# Radial-V_Bus.net
KiCad netlist of a schematic drawn in EAGLE
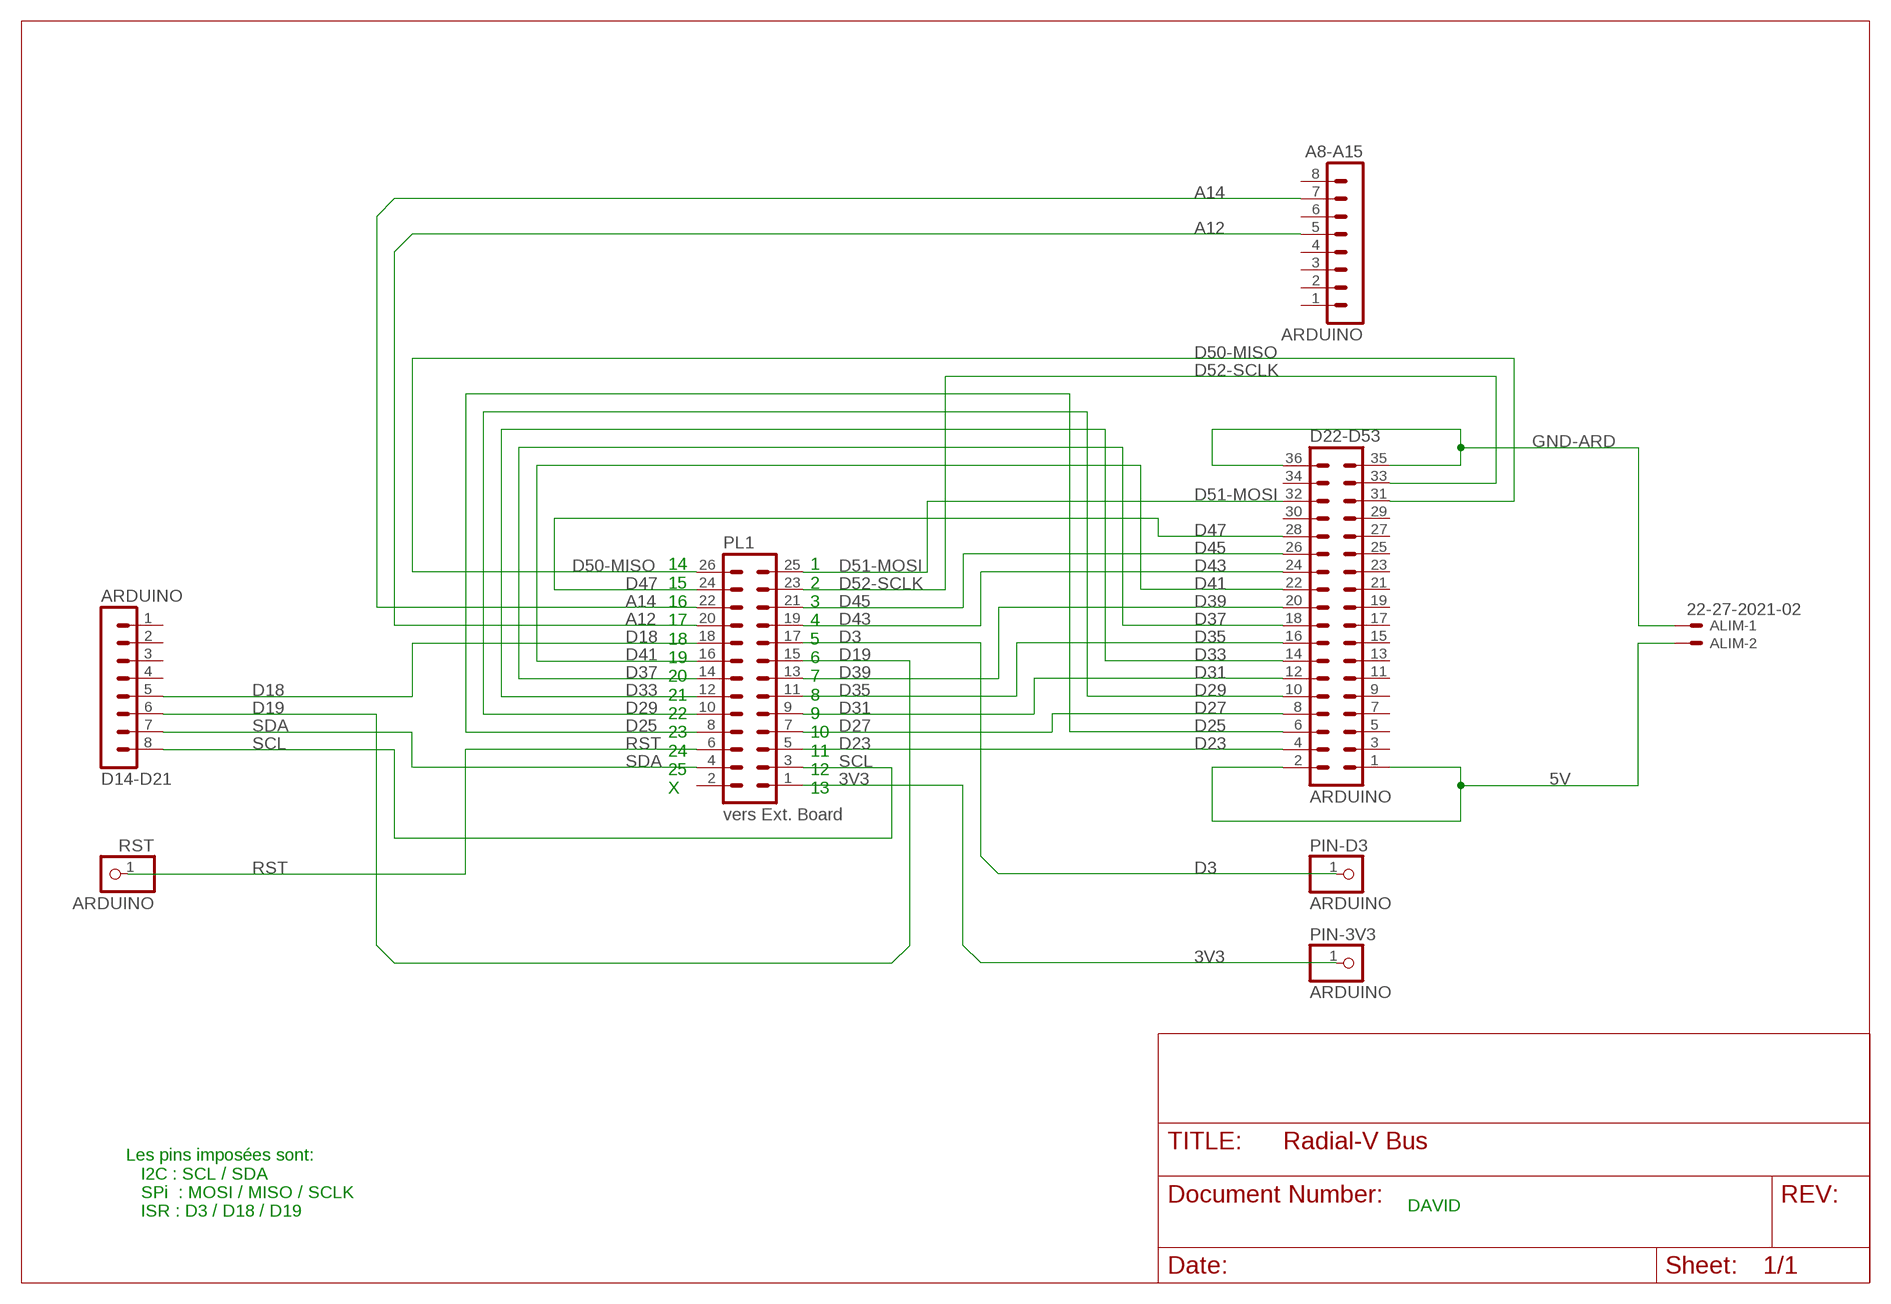
[diagram p0: schematic, sheet 1]

(export (version "E")
  (design (tool "Eeschema 10.0.6"))
  (components
    (comp (ref "A8-A15")
      (value "ARDUINO")
      (footprint "eagle-import:MA08-1")
      (libsource (lib "eagle-import") (part "MA08-1"))
    )
    (comp (ref "ALIM")
      (value "22-27-2021-02")
      (footprint "eagle-import:6410-02")
      (libsource (lib "eagle-import") (part "22-?-0227-2021"))
    )
    (comp (ref "D14-D21")
      (value "ARDUINO")
      (footprint "eagle-import:MA08-1")
      (libsource (lib "eagle-import") (part "MA08-1"))
    )
    (comp (ref "D22-D53")
      (value "ARDUINO")
      (footprint "eagle-import:MA18-2")
      (libsource (lib "eagle-import") (part "MA18-2"))
    )
    (comp (ref "PIN-3V3")
      (value "ARDUINO")
      (footprint "eagle-import:1X01")
      (libsource (lib "eagle-import") (part "PINHD-1X1"))
    )
    (comp (ref "PIN-D3")
      (value "ARDUINO")
      (footprint "eagle-import:1X01")
      (libsource (lib "eagle-import") (part "PINHD-1X1"))
    )
    (comp (ref "PL1")
      (value "vers Ext. Board")
      (footprint "eagle-import:26H")
      (libsource (lib "eagle-import") (part "26H"))
    )
    (comp (ref "RST")
      (value "ARDUINO")
      (footprint "eagle-import:1X01")
      (libsource (lib "eagle-import") (part "PINHD-1X1"))
    )
  )
  (nets
    (net (code "1") (name "/3V3") (class "Default")
      (node (ref "PIN-3V3") (pin "1") (pinfunction "1_1") (pintype "passive"))
      (node (ref "PL1") (pin "1") (pinfunction "1_1") (pintype "passive"))
    )
    (net (code "2") (name "/5V") (class "Default")
      (node (ref "ALIM") (pin "2") (pinfunction "S_2") (pintype "passive"))
      (node (ref "D22-D53") (pin "1") (pinfunction "1_1") (pintype "passive"))
      (node (ref "D22-D53") (pin "2") (pinfunction "2_2") (pintype "passive"))
    )
    (net (code "3") (name "/A12") (class "Default")
      (node (ref "A8-A15") (pin "5") (pinfunction "5_5") (pintype "passive"))
      (node (ref "PL1") (pin "20") (pinfunction "20_20") (pintype "passive"))
    )
    (net (code "4") (name "/A14") (class "Default")
      (node (ref "A8-A15") (pin "7") (pinfunction "7_7") (pintype "passive"))
      (node (ref "PL1") (pin "22") (pinfunction "22_22") (pintype "passive"))
    )
    (net (code "5") (name "/D3") (class "Default")
      (node (ref "PIN-D3") (pin "1") (pinfunction "1_1") (pintype "passive"))
      (node (ref "PL1") (pin "17") (pinfunction "17_17") (pintype "passive"))
    )
    (net (code "6") (name "/D18") (class "Default")
      (node (ref "D14-D21") (pin "5") (pinfunction "5_5") (pintype "passive"))
      (node (ref "PL1") (pin "18") (pinfunction "18_18") (pintype "passive"))
    )
    (net (code "7") (name "/D19") (class "Default")
      (node (ref "D14-D21") (pin "6") (pinfunction "6_6") (pintype "passive"))
      (node (ref "PL1") (pin "15") (pinfunction "15_15") (pintype "passive"))
    )
    (net (code "8") (name "/D23") (class "Default")
      (node (ref "D22-D53") (pin "4") (pinfunction "4_4") (pintype "passive"))
      (node (ref "PL1") (pin "5") (pinfunction "5_5") (pintype "passive"))
    )
    (net (code "9") (name "/D25") (class "Default")
      (node (ref "D22-D53") (pin "6") (pinfunction "6_6") (pintype "passive"))
      (node (ref "PL1") (pin "8") (pinfunction "8_8") (pintype "passive"))
    )
    (net (code "10") (name "/D27") (class "Default")
      (node (ref "D22-D53") (pin "8") (pinfunction "8_8") (pintype "passive"))
      (node (ref "PL1") (pin "7") (pinfunction "7_7") (pintype "passive"))
    )
    (net (code "11") (name "/D29") (class "Default")
      (node (ref "D22-D53") (pin "10") (pinfunction "10_10") (pintype "passive"))
      (node (ref "PL1") (pin "10") (pinfunction "10_10") (pintype "passive"))
    )
    (net (code "12") (name "/D31") (class "Default")
      (node (ref "D22-D53") (pin "12") (pinfunction "12_12") (pintype "passive"))
      (node (ref "PL1") (pin "9") (pinfunction "9_9") (pintype "passive"))
    )
    (net (code "13") (name "/D33") (class "Default")
      (node (ref "D22-D53") (pin "14") (pinfunction "14_14") (pintype "passive"))
      (node (ref "PL1") (pin "12") (pinfunction "12_12") (pintype "passive"))
    )
    (net (code "14") (name "/D35") (class "Default")
      (node (ref "D22-D53") (pin "16") (pinfunction "16_16") (pintype "passive"))
      (node (ref "PL1") (pin "11") (pinfunction "11_11") (pintype "passive"))
    )
    (net (code "15") (name "/D37") (class "Default")
      (node (ref "D22-D53") (pin "18") (pinfunction "18_18") (pintype "passive"))
      (node (ref "PL1") (pin "14") (pinfunction "14_14") (pintype "passive"))
    )
    (net (code "16") (name "/D39") (class "Default")
      (node (ref "D22-D53") (pin "20") (pinfunction "20_20") (pintype "passive"))
      (node (ref "PL1") (pin "13") (pinfunction "13_13") (pintype "passive"))
    )
    (net (code "17") (name "/D41") (class "Default")
      (node (ref "D22-D53") (pin "22") (pinfunction "22_22") (pintype "passive"))
      (node (ref "PL1") (pin "16") (pinfunction "16_16") (pintype "passive"))
    )
    (net (code "18") (name "/D43") (class "Default")
      (node (ref "D22-D53") (pin "24") (pinfunction "24_24") (pintype "passive"))
      (node (ref "PL1") (pin "19") (pinfunction "19_19") (pintype "passive"))
    )
    (net (code "19") (name "/D45") (class "Default")
      (node (ref "D22-D53") (pin "26") (pinfunction "26_26") (pintype "passive"))
      (node (ref "PL1") (pin "21") (pinfunction "21_21") (pintype "passive"))
    )
    (net (code "20") (name "/D47") (class "Default")
      (node (ref "D22-D53") (pin "28") (pinfunction "28_28") (pintype "passive"))
      (node (ref "PL1") (pin "24") (pinfunction "24_24") (pintype "passive"))
    )
    (net (code "21") (name "/D50-MISO") (class "Default")
      (node (ref "D22-D53") (pin "31") (pinfunction "31_31") (pintype "passive"))
      (node (ref "PL1") (pin "26") (pinfunction "26_26") (pintype "passive"))
    )
    (net (code "22") (name "/D51-MOSI") (class "Default")
      (node (ref "D22-D53") (pin "32") (pinfunction "32_32") (pintype "passive"))
      (node (ref "PL1") (pin "25") (pinfunction "25_25") (pintype "passive"))
    )
    (net (code "23") (name "/D52-SCLK") (class "Default")
      (node (ref "D22-D53") (pin "33") (pinfunction "33_33") (pintype "passive"))
      (node (ref "PL1") (pin "23") (pinfunction "23_23") (pintype "passive"))
    )
    (net (code "24") (name "/GND-ARD") (class "Default")
      (node (ref "ALIM") (pin "1") (pinfunction "S_1") (pintype "passive"))
      (node (ref "D22-D53") (pin "35") (pinfunction "35_35") (pintype "passive"))
      (node (ref "D22-D53") (pin "36") (pinfunction "36_36") (pintype "passive"))
    )
    (net (code "25") (name "/RST") (class "Default")
      (node (ref "PL1") (pin "6") (pinfunction "6_6") (pintype "passive"))
      (node (ref "RST") (pin "1") (pinfunction "1_1") (pintype "passive"))
    )
    (net (code "26") (name "/SCL") (class "Default")
      (node (ref "D14-D21") (pin "8") (pinfunction "8_8") (pintype "passive"))
      (node (ref "PL1") (pin "3") (pinfunction "3_3") (pintype "passive"))
    )
    (net (code "27") (name "/SDA") (class "Default")
      (node (ref "D14-D21") (pin "7") (pinfunction "7_7") (pintype "passive"))
      (node (ref "PL1") (pin "4") (pinfunction "4_4") (pintype "passive"))
    )
    (net (code "28") (name "unconnected-(A8-A15-Pad1)") (class "Default")
      (node (ref "A8-A15") (pin "1") (pinfunction "1_1") (pintype "passive"))
    )
    (net (code "29") (name "unconnected-(A8-A15-Pad2)") (class "Default")
      (node (ref "A8-A15") (pin "2") (pinfunction "2_2") (pintype "passive"))
    )
    (net (code "30") (name "unconnected-(A8-A15-Pad3)") (class "Default")
      (node (ref "A8-A15") (pin "3") (pinfunction "3_3") (pintype "passive"))
    )
    (net (code "31") (name "unconnected-(A8-A15-Pad4)") (class "Default")
      (node (ref "A8-A15") (pin "4") (pinfunction "4_4") (pintype "passive"))
    )
    (net (code "32") (name "unconnected-(A8-A15-Pad6)") (class "Default")
      (node (ref "A8-A15") (pin "6") (pinfunction "6_6") (pintype "passive"))
    )
    (net (code "33") (name "unconnected-(A8-A15-Pad8)") (class "Default")
      (node (ref "A8-A15") (pin "8") (pinfunction "8_8") (pintype "passive"))
    )
    (net (code "34") (name "unconnected-(D14-D21-Pad1)") (class "Default")
      (node (ref "D14-D21") (pin "1") (pinfunction "1_1") (pintype "passive"))
    )
    (net (code "35") (name "unconnected-(D14-D21-Pad2)") (class "Default")
      (node (ref "D14-D21") (pin "2") (pinfunction "2_2") (pintype "passive"))
    )
    (net (code "36") (name "unconnected-(D14-D21-Pad3)") (class "Default")
      (node (ref "D14-D21") (pin "3") (pinfunction "3_3") (pintype "passive"))
    )
    (net (code "37") (name "unconnected-(D14-D21-Pad4)") (class "Default")
      (node (ref "D14-D21") (pin "4") (pinfunction "4_4") (pintype "passive"))
    )
    (net (code "38") (name "unconnected-(D22-D53-Pad3)") (class "Default")
      (node (ref "D22-D53") (pin "3") (pinfunction "3_3") (pintype "passive"))
    )
    (net (code "39") (name "unconnected-(D22-D53-Pad5)") (class "Default")
      (node (ref "D22-D53") (pin "5") (pinfunction "5_5") (pintype "passive"))
    )
    (net (code "40") (name "unconnected-(D22-D53-Pad7)") (class "Default")
      (node (ref "D22-D53") (pin "7") (pinfunction "7_7") (pintype "passive"))
    )
    (net (code "41") (name "unconnected-(D22-D53-Pad9)") (class "Default")
      (node (ref "D22-D53") (pin "9") (pinfunction "9_9") (pintype "passive"))
    )
    (net (code "42") (name "unconnected-(D22-D53-Pad11)") (class "Default")
      (node (ref "D22-D53") (pin "11") (pinfunction "11_11") (pintype "passive"))
    )
    (net (code "43") (name "unconnected-(D22-D53-Pad13)") (class "Default")
      (node (ref "D22-D53") (pin "13") (pinfunction "13_13") (pintype "passive"))
    )
    (net (code "44") (name "unconnected-(D22-D53-Pad15)") (class "Default")
      (node (ref "D22-D53") (pin "15") (pinfunction "15_15") (pintype "passive"))
    )
    (net (code "45") (name "unconnected-(D22-D53-Pad17)") (class "Default")
      (node (ref "D22-D53") (pin "17") (pinfunction "17_17") (pintype "passive"))
    )
    (net (code "46") (name "unconnected-(D22-D53-Pad19)") (class "Default")
      (node (ref "D22-D53") (pin "19") (pinfunction "19_19") (pintype "passive"))
    )
    (net (code "47") (name "unconnected-(D22-D53-Pad21)") (class "Default")
      (node (ref "D22-D53") (pin "21") (pinfunction "21_21") (pintype "passive"))
    )
    (net (code "48") (name "unconnected-(D22-D53-Pad23)") (class "Default")
      (node (ref "D22-D53") (pin "23") (pinfunction "23_23") (pintype "passive"))
    )
    (net (code "49") (name "unconnected-(D22-D53-Pad25)") (class "Default")
      (node (ref "D22-D53") (pin "25") (pinfunction "25_25") (pintype "passive"))
    )
    (net (code "50") (name "unconnected-(D22-D53-Pad27)") (class "Default")
      (node (ref "D22-D53") (pin "27") (pinfunction "27_27") (pintype "passive"))
    )
    (net (code "51") (name "unconnected-(D22-D53-Pad29)") (class "Default")
      (node (ref "D22-D53") (pin "29") (pinfunction "29_29") (pintype "passive"))
    )
    (net (code "52") (name "unconnected-(D22-D53-Pad30)") (class "Default")
      (node (ref "D22-D53") (pin "30") (pinfunction "30_30") (pintype "passive"))
    )
    (net (code "53") (name "unconnected-(D22-D53-Pad34)") (class "Default")
      (node (ref "D22-D53") (pin "34") (pinfunction "34_34") (pintype "passive"))
    )
    (net (code "54") (name "unconnected-(PL1-Pad2)") (class "Default")
      (node (ref "PL1") (pin "2") (pinfunction "2_2") (pintype "passive"))
    )
  )
)
